# LumSensor.net
KiCad netlist of a schematic drawn in Altium Designer
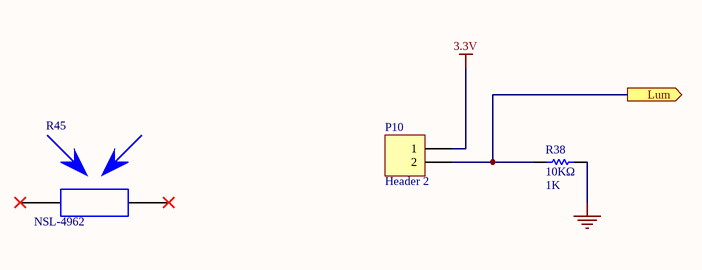
[diagram p0: LumSensor.SchDoc]

(export (version "E")
  (design (tool "Eeschema 10.0.6"))
  (components
    (comp (ref "P10")
      (value "Header 2")
      (footprint "BORNIER")
      (description "Header, 2-Pin")
      (fields
        (field (name "MANUFACTURER") "BUCHANAN - TE CONNECTIVITY")
        (field (name "PUBLISHER") "Altium Limited")
      )
      (libsource (lib "Miscellaneous Connectors") (part "Header 2"))
    )
    (comp (ref "R38")
      (value "10KΩ")
      (footprint "R0603")
      (description "Resistor")
      (fields (field (name "ALTIUM_VALUE") "1K") (field (name "PUBLISHER") "Altium Limited"))
      (libsource (lib "Miscellaneous Devices") (part "Res1"))
    )
    (comp (ref "R45")
      (value "NSL-4962")
      (footprint "NSL-4962")
      (description "Ldr")
      (fields (field (name "MANUFACTURER") "ADVANCED PHOTONIX"))
      (libsource (lib "Electroplant") (part "NSL-4962"))
    )
  )
  (nets
    (net (code "1") (name "/Lum") (class "Default")
      (node (ref "P10") (pin "2") (pinfunction "2_2") (pintype "passive"))
      (node (ref "R38") (pin "1") (pinfunction "1_1") (pintype "passive"))
    )
    (net (code "2") (name "3.3V") (class "Default")
      (node (ref "P10") (pin "1") (pinfunction "1_1") (pintype "passive"))
    )
    (net (code "3") (name "GND") (class "Default")
      (node (ref "R38") (pin "2") (pinfunction "2_2") (pintype "passive"))
    )
    (net (code "4") (name "unconnected-(R45-Pad1)") (class "Default")
      (node (ref "R45") (pin "1") (pinfunction "1_1") (pintype "passive+no_connect"))
    )
    (net (code "5") (name "unconnected-(R45-Pad2)") (class "Default")
      (node (ref "R45") (pin "2") (pinfunction "2_2") (pintype "passive+no_connect"))
    )
  )
)
